# midicontrol_v3.net
KiCad netlist of a schematic drawn in EAGLE
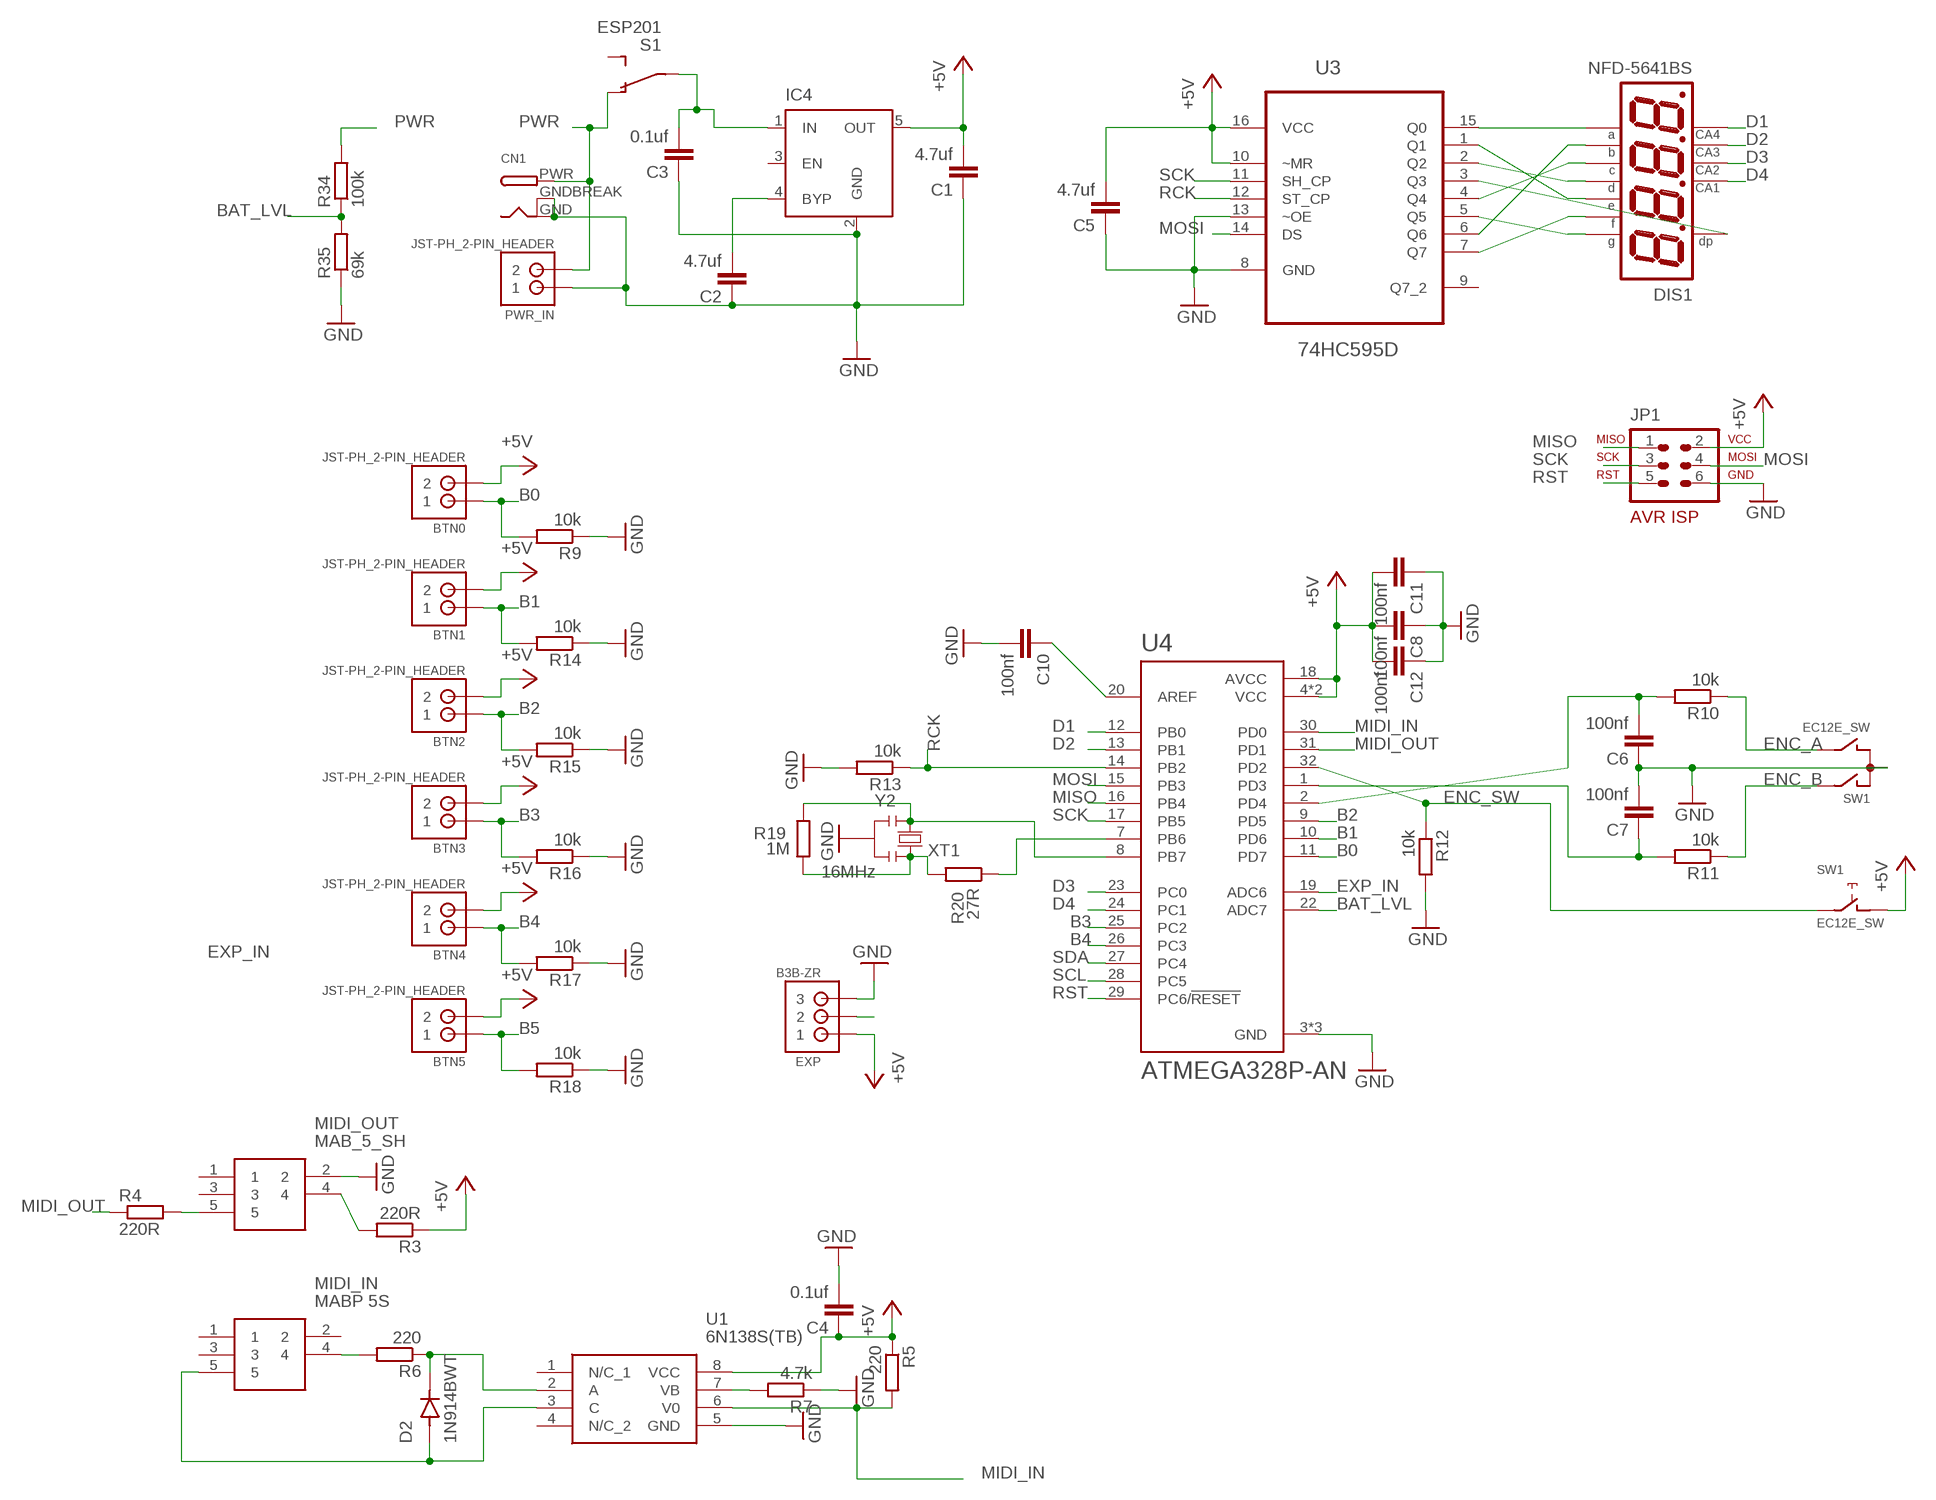
[diagram p0: schematic, sheet 1]

(export (version "E")
  (design (tool "Eeschema 10.0.6"))
  (components
    (comp (ref "BTN0")
      (value "JST-PH_2-PIN_HEADER")
      (footprint "eagle-import:JST_B2B-PH_HEADER")
      (libsource (lib "eagle-import") (part "JST-PH_2-PIN_HEADER"))
    )
    (comp (ref "BTN1")
      (value "JST-PH_2-PIN_HEADER")
      (footprint "eagle-import:JST_B2B-PH_HEADER")
      (libsource (lib "eagle-import") (part "JST-PH_2-PIN_HEADER"))
    )
    (comp (ref "BTN2")
      (value "JST-PH_2-PIN_HEADER")
      (footprint "eagle-import:JST_B2B-PH_HEADER")
      (libsource (lib "eagle-import") (part "JST-PH_2-PIN_HEADER"))
    )
    (comp (ref "BTN3")
      (value "JST-PH_2-PIN_HEADER")
      (footprint "eagle-import:JST_B2B-PH_HEADER")
      (libsource (lib "eagle-import") (part "JST-PH_2-PIN_HEADER"))
    )
    (comp (ref "BTN4")
      (value "JST-PH_2-PIN_HEADER")
      (footprint "eagle-import:JST_B2B-PH_HEADER")
      (libsource (lib "eagle-import") (part "JST-PH_2-PIN_HEADER"))
    )
    (comp (ref "BTN5")
      (value "JST-PH_2-PIN_HEADER")
      (footprint "eagle-import:JST_B2B-PH_HEADER")
      (libsource (lib "eagle-import") (part "JST-PH_2-PIN_HEADER"))
    )
    (comp (ref "C1")
      (value "4.7uf")
      (footprint "eagle-import:C1206")
      (libsource (lib "eagle-import") (part "C-EUC1206"))
    )
    (comp (ref "C2")
      (value "4.7uf")
      (footprint "eagle-import:C1206")
      (libsource (lib "eagle-import") (part "C-EUC1206"))
    )
    (comp (ref "C3")
      (value "0.1uf")
      (footprint "eagle-import:C1206")
      (libsource (lib "eagle-import") (part "C-EUC1206"))
    )
    (comp (ref "C4")
      (value "0.1uf")
      (footprint "eagle-import:C0603")
      (libsource (lib "eagle-import") (part "C-EUC0603"))
    )
    (comp (ref "C5")
      (value "4.7uf")
      (footprint "eagle-import:C0603")
      (libsource (lib "eagle-import") (part "C-EUC0603"))
    )
    (comp (ref "C6")
      (value "100nf")
      (footprint "eagle-import:C0603")
      (libsource (lib "eagle-import") (part "C-EUC0603"))
    )
    (comp (ref "C7")
      (value "100nf")
      (footprint "eagle-import:C0603")
      (libsource (lib "eagle-import") (part "C-EUC0603"))
    )
    (comp (ref "C8")
      (value "100nf")
      (footprint "eagle-import:C1206")
      (libsource (lib "eagle-import") (part "C-EUC1206"))
    )
    (comp (ref "C10")
      (value "100nf")
      (footprint "eagle-import:C0603")
      (libsource (lib "eagle-import") (part "C-EUC0603"))
    )
    (comp (ref "C11")
      (value "100nf")
      (footprint "eagle-import:C0603")
      (libsource (lib "eagle-import") (part "C-EUC0603"))
    )
    (comp (ref "C12")
      (value "100nf")
      (footprint "eagle-import:C0603")
      (libsource (lib "eagle-import") (part "C-EUC0603"))
    )
    (comp (ref "CN1")
      (value "DCBARRELPTH")
      (footprint "eagle-import:DCJACK_2MM_PTH")
      (libsource (lib "eagle-import") (part "DCBARRELPTH"))
    )
    (comp (ref "D2")
      (value "1N914BWT")
      (footprint "eagle-import:SODFL1608X70N")
      (fields (field (name "MF") "ON Semiconductor"))
      (libsource (lib "eagle-import") (part "1N914BWT"))
    )
    (comp (ref "DIS1")
      (value "NFD-5641BS")
      (footprint "eagle-import:NFD-5641")
      (libsource (lib "eagle-import") (part "NFD-5641BS"))
    )
    (comp (ref "EXP")
      (value "B3B-ZR")
      (footprint "eagle-import:B3B-ZR")
      (libsource (lib "eagle-import") (part "B3B-ZR"))
    )
    (comp (ref "IC4")
      (value "MIC5219XX")
      (footprint "eagle-import:SOT23-5")
      (libsource (lib "eagle-import") (part "MIC5219XX"))
    )
    (comp (ref "JP1")
      (value "AVR-ISP-6HORZ")
      (footprint "eagle-import:AVR-ISP-6R")
      (libsource (lib "eagle-import") (part "AVR-ISP-6HORZ"))
    )
    (comp (ref "MIDI_IN")
      (value "MABP 5S")
      (footprint "eagle-import:MAB-5-SH")
      (fields (field (name "MANUFACTURER_PART_NUMBER") "MAB 5 SH"))
      (libsource (lib "eagle-import") (part "MAB_5_SH"))
    )
    (comp (ref "MIDI_OUT")
      (value "MAB_5_SH")
      (footprint "eagle-import:MAB-5-SH")
      (fields (field (name "MANUFACTURER_PART_NUMBER") "MAB 5 SH"))
      (libsource (lib "eagle-import") (part "MAB_5_SH"))
    )
    (comp (ref "PWR_IN")
      (value "JST-PH_2-PIN_HEADER")
      (footprint "eagle-import:JST_B2B-PH_HEADER")
      (libsource (lib "eagle-import") (part "JST-PH_2-PIN_HEADER"))
    )
    (comp (ref "R3")
      (value "220R")
      (footprint "eagle-import:R0603")
      (libsource (lib "eagle-import") (part "rcl_334_R-EU_R0603"))
    )
    (comp (ref "R4")
      (value "220R")
      (footprint "eagle-import:R0603")
      (libsource (lib "eagle-import") (part "rcl_334_R-EU_R0603"))
    )
    (comp (ref "R5")
      (value "220")
      (footprint "eagle-import:R0603")
      (libsource (lib "eagle-import") (part "rcl_334_R-EU_R0603"))
    )
    (comp (ref "R6")
      (value "220")
      (footprint "eagle-import:R0603")
      (libsource (lib "eagle-import") (part "rcl_334_R-EU_R0603"))
    )
    (comp (ref "R7")
      (value "4.7k")
      (footprint "eagle-import:R0603")
      (libsource (lib "eagle-import") (part "rcl_334_R-EU_R0603"))
    )
    (comp (ref "R9")
      (value "10k")
      (footprint "eagle-import:R0603")
      (libsource (lib "eagle-import") (part "rcl_334_R-EU_R0603"))
    )
    (comp (ref "R10")
      (value "10k")
      (footprint "eagle-import:R0603")
      (libsource (lib "eagle-import") (part "rcl_334_R-EU_R0603"))
    )
    (comp (ref "R11")
      (value "10k")
      (footprint "eagle-import:R0603")
      (libsource (lib "eagle-import") (part "rcl_334_R-EU_R0603"))
    )
    (comp (ref "R12")
      (value "10k")
      (footprint "eagle-import:R0603")
      (libsource (lib "eagle-import") (part "rcl_334_R-EU_R0603"))
    )
    (comp (ref "R13")
      (value "10k")
      (footprint "eagle-import:R0603")
      (libsource (lib "eagle-import") (part "rcl_334_R-EU_R0603"))
    )
    (comp (ref "R14")
      (value "10k")
      (footprint "eagle-import:R0603")
      (libsource (lib "eagle-import") (part "rcl_334_R-EU_R0603"))
    )
    (comp (ref "R15")
      (value "10k")
      (footprint "eagle-import:R0603")
      (libsource (lib "eagle-import") (part "rcl_334_R-EU_R0603"))
    )
    (comp (ref "R16")
      (value "10k")
      (footprint "eagle-import:R0603")
      (libsource (lib "eagle-import") (part "rcl_334_R-EU_R0603"))
    )
    (comp (ref "R17")
      (value "10k")
      (footprint "eagle-import:R0603")
      (libsource (lib "eagle-import") (part "rcl_334_R-EU_R0603"))
    )
    (comp (ref "R18")
      (value "10k")
      (footprint "eagle-import:R0603")
      (libsource (lib "eagle-import") (part "rcl_334_R-EU_R0603"))
    )
    (comp (ref "R19")
      (value "1M")
      (footprint "eagle-import:R0603-ROUND")
      (libsource (lib "eagle-import") (part "R-EU_R0603"))
    )
    (comp (ref "R20")
      (value "27R")
      (footprint "eagle-import:R0603-ROUND")
      (libsource (lib "eagle-import") (part "R-EU_R0603"))
    )
    (comp (ref "R34")
      (value "100k")
      (footprint "eagle-import:R0603")
      (libsource (lib "eagle-import") (part "rcl_334_R-EU_R0603"))
    )
    (comp (ref "R35")
      (value "69k")
      (footprint "eagle-import:R0603")
      (libsource (lib "eagle-import") (part "rcl_334_R-EU_R0603"))
    )
    (comp (ref "S1")
      (value "ESP201")
      (footprint "eagle-import:ESP201")
      (libsource (lib "eagle-import") (part "ESP201"))
    )
    (comp (ref "SW1")
      (value "EC12E_SW")
      (footprint "eagle-import:ALPS_EC12E_SW")
      (fields (field (name "MPN") "EC12E2424407"))
      (libsource (lib "eagle-import") (part "EC12E_SW"))
    )
    (comp (ref "U1")
      (value "6N138S(TB)")
      (footprint "eagle-import:SOP254P1030X460-8N")
      (fields (field (name "MOUSER_PART_NUMBER") "638-6N138STB"))
      (libsource (lib "eagle-import") (part "6N138S(TB)"))
    )
    (comp (ref "U3")
      (value "74HC595D")
      (footprint "eagle-import:SOIC127P600X175-16N")
      (fields (field (name "MF") "Toshiba Semiconductor"))
      (libsource (lib "eagle-import") (part "74HC595D"))
    )
    (comp (ref "U4")
      (value "ATMEGA328P-AN")
      (footprint "eagle-import:QFP80P900X900X120-32N")
      (fields (field (name "MF") "Microchip"))
      (libsource (lib "eagle-import") (part "ATMEGA328P-AN"))
    )
    (comp (ref "Y2")
      (value "16MHz")
      (footprint "eagle-import:RESONATOR")
      (libsource (lib "eagle-import") (part "RESONATORMU"))
    )
  )
  (nets
    (net (code "1") (name "+5V") (class "Default")
      (node (ref "BTN0") (pin "P2") (pinfunction "2_P2") (pintype "bidirectional"))
      (node (ref "BTN1") (pin "P2") (pinfunction "2_P2") (pintype "bidirectional"))
      (node (ref "BTN2") (pin "P2") (pinfunction "2_P2") (pintype "bidirectional"))
      (node (ref "BTN3") (pin "P2") (pinfunction "2_P2") (pintype "bidirectional"))
      (node (ref "BTN4") (pin "P2") (pinfunction "2_P2") (pintype "bidirectional"))
      (node (ref "BTN5") (pin "P2") (pinfunction "2_P2") (pintype "bidirectional"))
      (node (ref "C1") (pin "2") (pinfunction "2_2") (pintype "passive"))
      (node (ref "C11") (pin "2") (pinfunction "2_2") (pintype "passive"))
      (node (ref "C12") (pin "2") (pinfunction "2_2") (pintype "passive"))
      (node (ref "C4") (pin "1") (pinfunction "1_1") (pintype "passive"))
      (node (ref "C5") (pin "2") (pinfunction "2_2") (pintype "passive"))
      (node (ref "C8") (pin "2") (pinfunction "2_2") (pintype "passive"))
      (node (ref "EXP") (pin "1") (pinfunction "1_1") (pintype "bidirectional"))
      (node (ref "IC4") (pin "5") (pinfunction "OUT_5") (pintype "output"))
      (node (ref "JP1") (pin "2") (pinfunction "2_2") (pintype "passive"))
      (node (ref "R3") (pin "1") (pinfunction "1_1") (pintype "passive"))
      (node (ref "R5") (pin "1") (pinfunction "1_1") (pintype "passive"))
      (node (ref "SW1") (pin "D") (pinfunction "1_D") (pintype "passive"))
      (node (ref "U1") (pin "8") (pinfunction "VCC_8") (pintype "power_in"))
      (node (ref "U3") (pin "10") (pinfunction "~{MR}_10") (pintype "passive"))
      (node (ref "U3") (pin "16") (pinfunction "VCC_16") (pintype "power_in"))
      (node (ref "U4") (pin "18") (pinfunction "AVCC_18") (pintype "power_in"))
      (node (ref "U4") (pin "4") (pinfunction "VCC_4") (pintype "power_in"))
      (node (ref "U4") (pin "6") (pinfunction "VCC_6") (pintype "power_in"))
    )
    (net (code "2") (name "/B0") (class "Default")
      (node (ref "BTN0") (pin "P1") (pinfunction "1_P1") (pintype "bidirectional"))
      (node (ref "R9") (pin "2") (pinfunction "2_2") (pintype "passive"))
      (node (ref "U4") (pin "11") (pinfunction "PD7_11") (pintype "bidirectional"))
    )
    (net (code "3") (name "/B1") (class "Default")
      (node (ref "BTN1") (pin "P1") (pinfunction "1_P1") (pintype "bidirectional"))
      (node (ref "R14") (pin "2") (pinfunction "2_2") (pintype "passive"))
      (node (ref "U4") (pin "10") (pinfunction "PD6_10") (pintype "bidirectional"))
    )
    (net (code "4") (name "/B2") (class "Default")
      (node (ref "BTN2") (pin "P1") (pinfunction "1_P1") (pintype "bidirectional"))
      (node (ref "R15") (pin "2") (pinfunction "2_2") (pintype "passive"))
      (node (ref "U4") (pin "9") (pinfunction "PD5_9") (pintype "bidirectional"))
    )
    (net (code "5") (name "/B3") (class "Default")
      (node (ref "BTN3") (pin "P1") (pinfunction "1_P1") (pintype "bidirectional"))
      (node (ref "R16") (pin "2") (pinfunction "2_2") (pintype "passive"))
      (node (ref "U4") (pin "25") (pinfunction "PC2_25") (pintype "bidirectional"))
    )
    (net (code "6") (name "/B4") (class "Default")
      (node (ref "BTN4") (pin "P1") (pinfunction "1_P1") (pintype "bidirectional"))
      (node (ref "R17") (pin "2") (pinfunction "2_2") (pintype "passive"))
      (node (ref "U4") (pin "26") (pinfunction "PC3_26") (pintype "bidirectional"))
    )
    (net (code "7") (name "/B5") (class "Default")
      (node (ref "BTN5") (pin "P1") (pinfunction "1_P1") (pintype "bidirectional"))
      (node (ref "R18") (pin "2") (pinfunction "2_2") (pintype "passive"))
    )
    (net (code "8") (name "/BAT_LVL") (class "Default")
      (node (ref "R34") (pin "1") (pinfunction "1_1") (pintype "passive"))
      (node (ref "R35") (pin "2") (pinfunction "2_2") (pintype "passive"))
      (node (ref "U4") (pin "22") (pinfunction "ADC7_22") (pintype "bidirectional"))
    )
    (net (code "9") (name "/D1") (class "Default")
      (node (ref "DIS1") (pin "P$6") (pinfunction "P$6_P$6") (pintype "bidirectional"))
      (node (ref "U4") (pin "12") (pinfunction "PB0_12") (pintype "bidirectional"))
    )
    (net (code "10") (name "/D2") (class "Default")
      (node (ref "DIS1") (pin "P$8") (pinfunction "P$8_P$8") (pintype "bidirectional"))
      (node (ref "U4") (pin "13") (pinfunction "PB1_13") (pintype "bidirectional"))
    )
    (net (code "11") (name "/D3") (class "Default")
      (node (ref "DIS1") (pin "P$9") (pinfunction "P$9_P$9") (pintype "bidirectional"))
      (node (ref "U4") (pin "23") (pinfunction "PC0_23") (pintype "bidirectional"))
    )
    (net (code "12") (name "/D4") (class "Default")
      (node (ref "DIS1") (pin "P$12") (pinfunction "P$12_P$12") (pintype "bidirectional"))
      (node (ref "U4") (pin "24") (pinfunction "PC1_24") (pintype "bidirectional"))
    )
    (net (code "13") (name "/ENC_A") (class "Default")
      (node (ref "R10") (pin "1") (pinfunction "1_1") (pintype "passive"))
      (node (ref "SW1") (pin "B") (pinfunction "B_B") (pintype "passive"))
    )
    (net (code "14") (name "/ENC_B") (class "Default")
      (node (ref "R11") (pin "1") (pinfunction "1_1") (pintype "passive"))
      (node (ref "SW1") (pin "A") (pinfunction "A_A") (pintype "passive"))
    )
    (net (code "15") (name "/ENC_SW") (class "Default")
      (node (ref "R12") (pin "1") (pinfunction "1_1") (pintype "passive"))
      (node (ref "SW1") (pin "E") (pinfunction "2_E") (pintype "passive"))
      (node (ref "U4") (pin "32") (pinfunction "PD2_32") (pintype "bidirectional"))
    )
    (net (code "16") (name "/EXP_IN") (class "Default")
      (node (ref "EXP") (pin "2") (pinfunction "2_2") (pintype "bidirectional"))
      (node (ref "U4") (pin "19") (pinfunction "ADC6_19") (pintype "bidirectional"))
    )
    (net (code "17") (name "/MIDI_IN") (class "Default")
      (node (ref "R5") (pin "2") (pinfunction "2_2") (pintype "passive"))
      (node (ref "U1") (pin "6") (pinfunction "V0_6") (pintype "bidirectional"))
      (node (ref "U4") (pin "30") (pinfunction "PD0_30") (pintype "bidirectional"))
    )
    (net (code "18") (name "/MIDI_OUT") (class "Default")
      (node (ref "R4") (pin "1") (pinfunction "1_1") (pintype "passive"))
      (node (ref "U4") (pin "31") (pinfunction "PD1_31") (pintype "bidirectional"))
    )
    (net (code "19") (name "/MISO") (class "Default")
      (node (ref "JP1") (pin "1") (pinfunction "1_1") (pintype "passive"))
      (node (ref "U4") (pin "16") (pinfunction "PB4_16") (pintype "bidirectional"))
    )
    (net (code "20") (name "/MOSI") (class "Default")
      (node (ref "JP1") (pin "4") (pinfunction "4_4") (pintype "passive"))
      (node (ref "U3") (pin "14") (pinfunction "DS_14") (pintype "input"))
      (node (ref "U4") (pin "15") (pinfunction "PB3_15") (pintype "bidirectional"))
    )
    (net (code "21") (name "/PWR") (class "Default")
      (node (ref "CN1") (pin "PWR") (pinfunction "PWR_PWR") (pintype "power_in"))
      (node (ref "PWR_IN") (pin "P2") (pinfunction "2_P2") (pintype "bidirectional"))
      (node (ref "R34") (pin "2") (pinfunction "2_2") (pintype "passive"))
      (node (ref "S1") (pin "P$3") (pinfunction "O_P$3") (pintype "passive"))
    )
    (net (code "22") (name "/RCK") (class "Default")
      (node (ref "R13") (pin "1") (pinfunction "1_1") (pintype "passive"))
      (node (ref "U3") (pin "12") (pinfunction "ST_CP_12") (pintype "passive"))
      (node (ref "U4") (pin "14") (pinfunction "PB2_14") (pintype "bidirectional"))
    )
    (net (code "23") (name "/RST") (class "Default")
      (node (ref "JP1") (pin "5") (pinfunction "5_5") (pintype "passive"))
      (node (ref "U4") (pin "29") (pinfunction "PC6/~{RESET}_29") (pintype "bidirectional"))
    )
    (net (code "24") (name "/SCK") (class "Default")
      (node (ref "JP1") (pin "3") (pinfunction "3_3") (pintype "passive"))
      (node (ref "U3") (pin "11") (pinfunction "SH_CP_11") (pintype "passive"))
      (node (ref "U4") (pin "17") (pinfunction "PB5_17") (pintype "bidirectional"))
    )
    (net (code "25") (name "/SCL") (class "Default")
      (node (ref "U4") (pin "28") (pinfunction "PC5_28") (pintype "bidirectional"))
    )
    (net (code "26") (name "/SDA") (class "Default")
      (node (ref "U4") (pin "27") (pinfunction "PC4_27") (pintype "bidirectional"))
    )
    (net (code "27") (name "/XT1") (class "Default")
      (node (ref "R19") (pin "1") (pinfunction "1_1") (pintype "passive"))
      (node (ref "R20") (pin "2") (pinfunction "2_2") (pintype "passive"))
      (node (ref "Y2") (pin "3") (pinfunction "3_3") (pintype "passive"))
    )
    (net (code "28") (name "GND") (class "Default")
      (node (ref "C1") (pin "1") (pinfunction "1_1") (pintype "passive"))
      (node (ref "C10") (pin "2") (pinfunction "2_2") (pintype "passive"))
      (node (ref "C11") (pin "1") (pinfunction "1_1") (pintype "passive"))
      (node (ref "C12") (pin "1") (pinfunction "1_1") (pintype "passive"))
      (node (ref "C2") (pin "1") (pinfunction "1_1") (pintype "passive"))
      (node (ref "C3") (pin "1") (pinfunction "1_1") (pintype "passive"))
      (node (ref "C4") (pin "2") (pinfunction "2_2") (pintype "passive"))
      (node (ref "C5") (pin "1") (pinfunction "1_1") (pintype "passive"))
      (node (ref "C6") (pin "1") (pinfunction "1_1") (pintype "passive"))
      (node (ref "C7") (pin "2") (pinfunction "2_2") (pintype "passive"))
      (node (ref "C8") (pin "1") (pinfunction "1_1") (pintype "passive"))
      (node (ref "CN1") (pin "GND") (pinfunction "GND_GND") (pintype "power_in"))
      (node (ref "CN1") (pin "GNDBREAK") (pinfunction "GNDBREAK_GNDBREAK") (pintype "power_in"))
      (node (ref "EXP") (pin "3") (pinfunction "3_3") (pintype "bidirectional"))
      (node (ref "IC4") (pin "2") (pinfunction "GND_2") (pintype "power_in"))
      (node (ref "JP1") (pin "6") (pinfunction "6_6") (pintype "passive"))
      (node (ref "MIDI_OUT") (pin "2") (pinfunction "2_2") (pintype "bidirectional"))
      (node (ref "PWR_IN") (pin "P1") (pinfunction "1_P1") (pintype "bidirectional"))
      (node (ref "R12") (pin "2") (pinfunction "2_2") (pintype "passive"))
      (node (ref "R13") (pin "2") (pinfunction "2_2") (pintype "passive"))
      (node (ref "R14") (pin "1") (pinfunction "1_1") (pintype "passive"))
      (node (ref "R15") (pin "1") (pinfunction "1_1") (pintype "passive"))
      (node (ref "R16") (pin "1") (pinfunction "1_1") (pintype "passive"))
      (node (ref "R17") (pin "1") (pinfunction "1_1") (pintype "passive"))
      (node (ref "R18") (pin "1") (pinfunction "1_1") (pintype "passive"))
      (node (ref "R35") (pin "1") (pinfunction "1_1") (pintype "passive"))
      (node (ref "R7") (pin "1") (pinfunction "1_1") (pintype "passive"))
      (node (ref "R9") (pin "1") (pinfunction "1_1") (pintype "passive"))
      (node (ref "SW1") (pin "C") (pinfunction "C_C") (pintype "passive"))
      (node (ref "U1") (pin "5") (pinfunction "GND_5") (pintype "power_in"))
      (node (ref "U3") (pin "13") (pinfunction "~{OE}_13") (pintype "input"))
      (node (ref "U3") (pin "8") (pinfunction "GND_8") (pintype "passive"))
      (node (ref "U4") (pin "21") (pinfunction "GND_21") (pintype "power_in"))
      (node (ref "U4") (pin "3") (pinfunction "GND_3") (pintype "power_in"))
      (node (ref "U4") (pin "5") (pinfunction "GND_5") (pintype "power_in"))
      (node (ref "Y2") (pin "2") (pinfunction "2_2") (pintype "passive"))
    )
    (net (code "29") (name "Net-(D2-K)") (class "Default")
      (node (ref "D2") (pin "C") (pinfunction "K_C") (pintype "passive"))
      (node (ref "R6") (pin "1") (pinfunction "1_1") (pintype "passive"))
      (node (ref "U1") (pin "2") (pinfunction "A_2") (pintype "bidirectional"))
    )
    (net (code "30") (name "Net-(IC4-BYP)") (class "Default")
      (node (ref "C2") (pin "2") (pinfunction "2_2") (pintype "passive"))
      (node (ref "IC4") (pin "4") (pinfunction "BYP_4") (pintype "passive"))
    )
    (net (code "31") (name "Net-(IC4-IN)") (class "Default")
      (node (ref "C3") (pin "2") (pinfunction "2_2") (pintype "passive"))
      (node (ref "IC4") (pin "1") (pinfunction "IN_1") (pintype "input"))
      (node (ref "S1") (pin "P$1") (pinfunction "P_P$1") (pintype "passive"))
    )
    (net (code "32") (name "Net-(MIDI_IN-Pad4)") (class "Default")
      (node (ref "MIDI_IN") (pin "4") (pinfunction "4_4") (pintype "bidirectional"))
      (node (ref "R6") (pin "2") (pinfunction "2_2") (pintype "passive"))
    )
    (net (code "33") (name "Net-(MIDI_OUT-Pad4)") (class "Default")
      (node (ref "MIDI_OUT") (pin "4") (pinfunction "4_4") (pintype "bidirectional"))
      (node (ref "R3") (pin "2") (pinfunction "2_2") (pintype "passive"))
    )
    (net (code "34") (name "Net-(MIDI_OUT-Pad5)") (class "Default")
      (node (ref "MIDI_OUT") (pin "5") (pinfunction "5_5") (pintype "bidirectional"))
      (node (ref "R4") (pin "2") (pinfunction "2_2") (pintype "passive"))
    )
    (net (code "35") (name "Net-(U1-C)") (class "Default")
      (node (ref "D2") (pin "A") (pinfunction "A_A") (pintype "passive"))
      (node (ref "MIDI_IN") (pin "5") (pinfunction "5_5") (pintype "bidirectional"))
      (node (ref "U1") (pin "3") (pinfunction "C_3") (pintype "bidirectional"))
    )
    (net (code "36") (name "Net-(U1-VB)") (class "Default")
      (node (ref "R7") (pin "2") (pinfunction "2_2") (pintype "passive"))
      (node (ref "U1") (pin "7") (pinfunction "VB_7") (pintype "bidirectional"))
    )
    (net (code "37") (name "Net-(U3-Q0)") (class "Default")
      (node (ref "DIS1") (pin "P$11") (pinfunction "P$11_P$11") (pintype "bidirectional"))
      (node (ref "U3") (pin "15") (pinfunction "Q0_15") (pintype "output"))
    )
    (net (code "38") (name "Net-(U3-Q1)") (class "Default")
      (node (ref "DIS1") (pin "P$1") (pinfunction "P$1_P$1") (pintype "bidirectional"))
      (node (ref "U3") (pin "1") (pinfunction "Q1_1") (pintype "output"))
    )
    (net (code "39") (name "Net-(U3-Q2)") (class "Default")
      (node (ref "DIS1") (pin "P$2") (pinfunction "P$2_P$2") (pintype "bidirectional"))
      (node (ref "U3") (pin "2") (pinfunction "Q2_2") (pintype "output"))
    )
    (net (code "40") (name "Net-(U3-Q3)") (class "Default")
      (node (ref "DIS1") (pin "P$3") (pinfunction "P$3_P$3") (pintype "bidirectional"))
      (node (ref "U3") (pin "3") (pinfunction "Q3_3") (pintype "output"))
    )
    (net (code "41") (name "Net-(U3-Q4)") (class "Default")
      (node (ref "DIS1") (pin "P$4") (pinfunction "P$4_P$4") (pintype "bidirectional"))
      (node (ref "U3") (pin "4") (pinfunction "Q4_4") (pintype "output"))
    )
    (net (code "42") (name "Net-(U3-Q5)") (class "Default")
      (node (ref "DIS1") (pin "P$5") (pinfunction "P$5_P$5") (pintype "bidirectional"))
      (node (ref "U3") (pin "5") (pinfunction "Q5_5") (pintype "output"))
    )
    (net (code "43") (name "Net-(U3-Q6)") (class "Default")
      (node (ref "DIS1") (pin "P$7") (pinfunction "P$7_P$7") (pintype "bidirectional"))
      (node (ref "U3") (pin "6") (pinfunction "Q6_6") (pintype "output"))
    )
    (net (code "44") (name "Net-(U3-Q7)") (class "Default")
      (node (ref "DIS1") (pin "P$10") (pinfunction "P$10_P$10") (pintype "bidirectional"))
      (node (ref "U3") (pin "7") (pinfunction "Q7_7") (pintype "output"))
    )
    (net (code "45") (name "Net-(U4-AREF)") (class "Default")
      (node (ref "C10") (pin "1") (pinfunction "1_1") (pintype "passive"))
      (node (ref "U4") (pin "20") (pinfunction "AREF_20") (pintype "input"))
    )
    (net (code "46") (name "Net-(U4-PB6)") (class "Default")
      (node (ref "R20") (pin "1") (pinfunction "1_1") (pintype "passive"))
      (node (ref "U4") (pin "7") (pinfunction "PB6_7") (pintype "bidirectional"))
    )
    (net (code "47") (name "Net-(U4-PB7)") (class "Default")
      (node (ref "R19") (pin "2") (pinfunction "2_2") (pintype "passive"))
      (node (ref "U4") (pin "8") (pinfunction "PB7_8") (pintype "bidirectional"))
      (node (ref "Y2") (pin "1") (pinfunction "1_1") (pintype "passive"))
    )
    (net (code "48") (name "Net-(U4-PD3)") (class "Default")
      (node (ref "C7") (pin "1") (pinfunction "1_1") (pintype "passive"))
      (node (ref "R11") (pin "2") (pinfunction "2_2") (pintype "passive"))
      (node (ref "U4") (pin "1") (pinfunction "PD3_1") (pintype "bidirectional"))
    )
    (net (code "49") (name "Net-(U4-PD4)") (class "Default")
      (node (ref "C6") (pin "2") (pinfunction "2_2") (pintype "passive"))
      (node (ref "R10") (pin "2") (pinfunction "2_2") (pintype "passive"))
      (node (ref "U4") (pin "2") (pinfunction "PD4_2") (pintype "bidirectional"))
    )
    (net (code "50") (name "unconnected-(IC4-EN-Pad3)") (class "Default")
      (node (ref "IC4") (pin "3") (pinfunction "EN_3") (pintype "input"))
    )
    (net (code "51") (name "unconnected-(MIDI_IN-Pad1)") (class "Default")
      (node (ref "MIDI_IN") (pin "1") (pinfunction "1_1") (pintype "bidirectional"))
    )
    (net (code "52") (name "unconnected-(MIDI_IN-Pad2)") (class "Default")
      (node (ref "MIDI_IN") (pin "2") (pinfunction "2_2") (pintype "bidirectional"))
    )
    (net (code "53") (name "unconnected-(MIDI_IN-Pad3)") (class "Default")
      (node (ref "MIDI_IN") (pin "3") (pinfunction "3_3") (pintype "bidirectional"))
    )
    (net (code "54") (name "unconnected-(MIDI_OUT-Pad1)") (class "Default")
      (node (ref "MIDI_OUT") (pin "1") (pinfunction "1_1") (pintype "bidirectional"))
    )
    (net (code "55") (name "unconnected-(MIDI_OUT-Pad3)") (class "Default")
      (node (ref "MIDI_OUT") (pin "3") (pinfunction "3_3") (pintype "bidirectional"))
    )
    (net (code "56") (name "unconnected-(S1-S-PadP$2)") (class "Default")
      (node (ref "S1") (pin "P$2") (pinfunction "S_P$2") (pintype "passive"))
    )
    (net (code "57") (name "unconnected-(U1-N{slash}C_1-Pad1)") (class "Default")
      (node (ref "U1") (pin "1") (pinfunction "N/C_1_1") (pintype "bidirectional"))
    )
    (net (code "58") (name "unconnected-(U1-N{slash}C_2-Pad4)") (class "Default")
      (node (ref "U1") (pin "4") (pinfunction "N/C_2_4") (pintype "bidirectional"))
    )
    (net (code "59") (name "unconnected-(U3-Q7_2-Pad9)") (class "Default")
      (node (ref "U3") (pin "9") (pinfunction "Q7_2_9") (pintype "output"))
    )
  )
)
